# HT62N_v1_1.net
KiCad netlist of a schematic drawn in Altium Designer
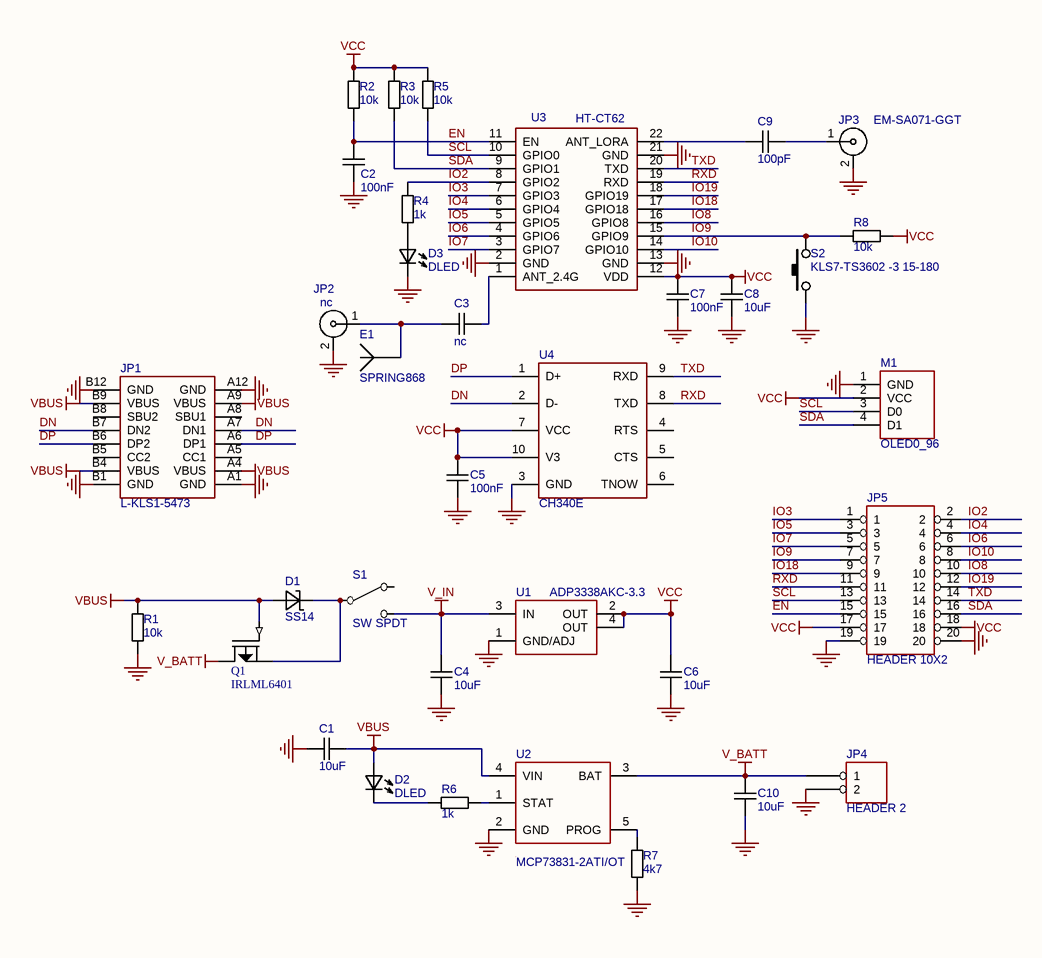
[diagram p0: HT62N_v1.1.SchDoc]

(export (version "E")
  (design (tool "Eeschema 10.0.6"))
  (components
    (comp (ref "C1")
      (value "10uF")
      (footprint "C-0805")
      (fields (field (name "VOLTAGE") "50V"))
      (libsource (lib "Passive") (part "CAPN"))
    )
    (comp (ref "C2")
      (value "100nF")
      (footprint "C-0603")
      (fields (field (name "VOLTAGE") "50V"))
      (libsource (lib "Passive") (part "CAPN"))
    )
    (comp (ref "C3")
      (value "nc")
      (footprint "C-0603")
      (fields (field (name "VOLTAGE") "50V"))
      (libsource (lib "Passive") (part "CAPN"))
    )
    (comp (ref "C4")
      (value "10uF")
      (footprint "C-0805")
      (fields (field (name "VOLTAGE") "50V"))
      (libsource (lib "Passive") (part "CAPN"))
    )
    (comp (ref "C5")
      (value "100nF")
      (footprint "C-0603")
      (fields (field (name "VOLTAGE") "50V"))
      (libsource (lib "Passive") (part "CAPN"))
    )
    (comp (ref "C6")
      (value "10uF")
      (footprint "C-0805")
      (fields (field (name "VOLTAGE") "50V"))
      (libsource (lib "Passive") (part "CAPN"))
    )
    (comp (ref "C7")
      (value "100nF")
      (footprint "C-0603")
      (fields (field (name "VOLTAGE") "50V"))
      (libsource (lib "Passive") (part "CAPN"))
    )
    (comp (ref "C8")
      (value "10uF")
      (footprint "C-0805")
      (fields (field (name "VOLTAGE") "50V"))
      (libsource (lib "Passive") (part "CAPN"))
    )
    (comp (ref "C9")
      (value "100pF")
      (footprint "C-0603")
      (fields (field (name "VOLTAGE") "50V"))
      (libsource (lib "Passive") (part "CAPN"))
    )
    (comp (ref "C10")
      (value "10uF")
      (footprint "C-0805")
      (fields (field (name "VOLTAGE") "50V"))
      (libsource (lib "Passive") (part "CAPN"))
    )
    (comp (ref "D1") (value "SS14") (footprint "D-SMA") (libsource (lib "Diodes") (part "DIODSH")))
    (comp (ref "D2") (value "DLED") (footprint "LED_3mm_RED") (libsource (lib "Diodes") (part "DLED")))
    (comp (ref "D3") (value "DLED") (footprint "LED_3mm_RED") (libsource (lib "Diodes") (part "DLED")))
    (comp (ref "E1") (value "SPRING868") (footprint "ANT_H868_V") (libsource (lib "Passive") (part "ANT")))
    (comp (ref "JP1")
      (value "L-KLS1-5473")
      (footprint "USB_C_SMD_SLOT")
      (libsource (lib "Connectors") (part "L-KLS1-5473"))
    )
    (comp (ref "JP2")
      (value "nc")
      (footprint "SMA_F_EDGE")
      (description "SMA Female R/A PCB Mount")
      (libsource (lib "Connectors") (part "SMA"))
    )
    (comp (ref "JP3")
      (value "EM-SA071-GGT")
      (footprint "SMA_F_EDGE")
      (description "SMA Female R/A PCB Mount")
      (libsource (lib "Connectors") (part "SMA"))
    )
    (comp (ref "JP4")
      (value "HEADER 2")
      (footprint "PLS1-2")
      (libsource (lib "Connectors") (part "HEADER 2"))
    )
    (comp (ref "JP5")
      (value "HEADER 10X2")
      (footprint "PLS2_10")
      (libsource (lib "Connectors") (part "HEADER 10X2"))
    )
    (comp (ref "M1")
      (value "OLED0_96")
      (footprint "OLED096_I2C")
      (libsource (lib "RFmodules") (part "OLED0_96_I2C"))
    )
    (comp (ref "Q1") (value "IRLML6401") (footprint "SOT-23") (libsource (lib "Discrete") (part "MOSF-P")))
    (comp (ref "R1") (value "10k") (footprint "R-0603") (libsource (lib "") (part "RES_2")))
    (comp (ref "R2") (value "10k") (footprint "R-0603") (libsource (lib "Passive") (part "RES")))
    (comp (ref "R3") (value "10k") (footprint "R-0603") (libsource (lib "Passive") (part "RES")))
    (comp (ref "R4") (value "1k") (footprint "R-0603") (libsource (lib "") (part "RES_2")))
    (comp (ref "R5") (value "10k") (footprint "R-0603") (libsource (lib "Passive") (part "RES")))
    (comp (ref "R6") (value "1k") (footprint "R-0603") (libsource (lib "") (part "RES_1")))
    (comp (ref "R7") (value "4k7") (footprint "R-0603") (libsource (lib "") (part "RES_2")))
    (comp (ref "R8") (value "10k") (footprint "R-0603") (libsource (lib "") (part "RES_1")))
    (comp (ref "S1")
      (value "SW SPDT")
      (footprint "SK-12D07VG5")
      (libsource (lib "Switches") (part "SW SPDT"))
    )
    (comp (ref "S2")
      (value "KLS7-TS3602 -3 15-180")
      (footprint "KLS7-TS3602")
      (libsource (lib "Switches") (part "SW-1"))
    )
    (comp (ref "U1")
      (value "ADP3338AKC-3.3")
      (footprint "SOT223")
      (description "LOW CURRENT ADJUSTABLE  VOLTAGE REGULATOR")
      (libsource (lib "ICs") (part "LDL1117"))
    )
    (comp (ref "U2")
      (value "MCP73831-2ATI/OT")
      (footprint "SOT-23-5")
      (fields
        (field (name "LIBRARY PART") "IC`s.SchLib")
        (field (name "FOOTPRINT PART") "IC-package.PcbLib")
        (field (name "MANUFACTURER") "Texas Instruments")
      )
      (libsource (lib "ICs") (part "MCP73831-2ATI/OT"))
    )
    (comp (ref "U3") (value "HT-CT62") (footprint "HT-CT62") (libsource (lib "RFmodules") (part "HT-CT62")))
    (comp (ref "U4") (value "CH340E") (footprint "MSOP-10") (libsource (lib "ICs") (part "CH340E")))
  )
  (nets
    (net (code "1") (name "/DN") (class "Default")
      (node (ref "JP1") (pin "A7") (pinfunction "DN1_A7") (pintype "passive"))
      (node (ref "JP1") (pin "B7") (pinfunction "DN2_B7") (pintype "passive"))
      (node (ref "U4") (pin "2") (pinfunction "D-_2") (pintype "passive"))
    )
    (net (code "2") (name "/DP") (class "Default")
      (node (ref "JP1") (pin "A6") (pinfunction "DP1_A6") (pintype "passive"))
      (node (ref "JP1") (pin "B6") (pinfunction "DP2_B6") (pintype "passive"))
      (node (ref "U4") (pin "1") (pinfunction "D+_1") (pintype "passive"))
    )
    (net (code "3") (name "/EN") (class "Default")
      (node (ref "C2") (pin "2") (pinfunction "2_2") (pintype "passive"))
      (node (ref "JP5") (pin "15") (pinfunction "15_15") (pintype "passive"))
      (node (ref "R2") (pin "2") (pinfunction "2_2") (pintype "passive"))
      (node (ref "U3") (pin "11") (pinfunction "EN_11") (pintype "passive"))
    )
    (net (code "4") (name "/IO2") (class "Default")
      (node (ref "JP5") (pin "2") (pinfunction "2_2") (pintype "passive"))
      (node (ref "R4") (pin "2") (pinfunction "2_2") (pintype "passive"))
      (node (ref "U3") (pin "8") (pinfunction "GPIO2_8") (pintype "passive"))
    )
    (net (code "5") (name "/IO3") (class "Default")
      (node (ref "JP5") (pin "1") (pinfunction "1_1") (pintype "passive"))
      (node (ref "U3") (pin "7") (pinfunction "GPIO3_7") (pintype "passive"))
    )
    (net (code "6") (name "/IO4") (class "Default")
      (node (ref "JP5") (pin "4") (pinfunction "4_4") (pintype "passive"))
      (node (ref "U3") (pin "6") (pinfunction "GPIO4_6") (pintype "passive"))
    )
    (net (code "7") (name "/IO5") (class "Default")
      (node (ref "JP5") (pin "3") (pinfunction "3_3") (pintype "passive"))
      (node (ref "U3") (pin "5") (pinfunction "GPIO5_5") (pintype "passive"))
    )
    (net (code "8") (name "/IO6") (class "Default")
      (node (ref "JP5") (pin "6") (pinfunction "6_6") (pintype "passive"))
      (node (ref "U3") (pin "4") (pinfunction "GPIO6_4") (pintype "passive"))
    )
    (net (code "9") (name "/IO7") (class "Default")
      (node (ref "JP5") (pin "5") (pinfunction "5_5") (pintype "passive"))
      (node (ref "U3") (pin "3") (pinfunction "GPIO7_3") (pintype "passive"))
    )
    (net (code "10") (name "/IO8") (class "Default")
      (node (ref "JP5") (pin "10") (pinfunction "10_10") (pintype "passive"))
      (node (ref "U3") (pin "16") (pinfunction "GPIO8_16") (pintype "passive"))
    )
    (net (code "11") (name "/IO9") (class "Default")
      (node (ref "JP5") (pin "7") (pinfunction "7_7") (pintype "passive"))
      (node (ref "R8") (pin "2") (pinfunction "2_2") (pintype "passive"))
      (node (ref "S2") (pin "2") (pinfunction "2_2") (pintype "passive"))
      (node (ref "U3") (pin "15") (pinfunction "GPIO9_15") (pintype "passive"))
    )
    (net (code "12") (name "/IO10") (class "Default")
      (node (ref "JP5") (pin "8") (pinfunction "8_8") (pintype "passive"))
      (node (ref "U3") (pin "14") (pinfunction "GPIO10_14") (pintype "passive"))
    )
    (net (code "13") (name "/IO18") (class "Default")
      (node (ref "JP5") (pin "9") (pinfunction "9_9") (pintype "passive"))
      (node (ref "U3") (pin "17") (pinfunction "GPIO18_17") (pintype "passive"))
    )
    (net (code "14") (name "/IO19") (class "Default")
      (node (ref "JP5") (pin "12") (pinfunction "12_12") (pintype "passive"))
      (node (ref "U3") (pin "18") (pinfunction "GPIO19_18") (pintype "passive"))
    )
    (net (code "15") (name "/RXD") (class "Default")
      (node (ref "JP5") (pin "11") (pinfunction "11_11") (pintype "passive"))
      (node (ref "U3") (pin "19") (pinfunction "RXD_19") (pintype "passive"))
      (node (ref "U4") (pin "8") (pinfunction "TXD_8") (pintype "passive"))
    )
    (net (code "16") (name "/SCL") (class "Default")
      (node (ref "JP5") (pin "13") (pinfunction "13_13") (pintype "passive"))
      (node (ref "M1") (pin "3") (pinfunction "D0_3") (pintype "passive"))
      (node (ref "R5") (pin "2") (pinfunction "2_2") (pintype "passive"))
      (node (ref "U3") (pin "10") (pinfunction "GPIO0_10") (pintype "passive"))
    )
    (net (code "17") (name "/SDA") (class "Default")
      (node (ref "JP5") (pin "16") (pinfunction "16_16") (pintype "passive"))
      (node (ref "M1") (pin "4") (pinfunction "D1_4") (pintype "passive"))
      (node (ref "R3") (pin "2") (pinfunction "2_2") (pintype "passive"))
      (node (ref "U3") (pin "9") (pinfunction "GPIO1_9") (pintype "passive"))
    )
    (net (code "18") (name "/TXD") (class "Default")
      (node (ref "JP5") (pin "14") (pinfunction "14_14") (pintype "passive"))
      (node (ref "U3") (pin "20") (pinfunction "TXD_20") (pintype "passive"))
      (node (ref "U4") (pin "9") (pinfunction "RXD_9") (pintype "passive"))
    )
    (net (code "19") (name "GND") (class "Default")
      (node (ref "C1") (pin "1") (pinfunction "1_1") (pintype "passive"))
      (node (ref "C10") (pin "1") (pinfunction "1_1") (pintype "passive"))
      (node (ref "C2") (pin "1") (pinfunction "1_1") (pintype "passive"))
      (node (ref "C4") (pin "2") (pinfunction "2_2") (pintype "passive"))
      (node (ref "C5") (pin "1") (pinfunction "1_1") (pintype "passive"))
      (node (ref "C6") (pin "2") (pinfunction "2_2") (pintype "passive"))
      (node (ref "C7") (pin "1") (pinfunction "1_1") (pintype "passive"))
      (node (ref "C8") (pin "2") (pinfunction "2_2") (pintype "passive"))
      (node (ref "D3") (pin "2") (pinfunction "2_2") (pintype "passive"))
      (node (ref "JP1") (pin "A1") (pinfunction "GND_A1") (pintype "passive"))
      (node (ref "JP1") (pin "A12") (pinfunction "GND_A12") (pintype "passive"))
      (node (ref "JP1") (pin "B1") (pinfunction "GND_B1") (pintype "passive"))
      (node (ref "JP1") (pin "B12") (pinfunction "GND_B12") (pintype "passive"))
      (node (ref "JP2") (pin "2") (pinfunction "2_2") (pintype "passive"))
      (node (ref "JP3") (pin "2") (pinfunction "2_2") (pintype "passive"))
      (node (ref "JP4") (pin "2") (pinfunction "2_2") (pintype "passive"))
      (node (ref "JP5") (pin "19") (pinfunction "19_19") (pintype "passive"))
      (node (ref "JP5") (pin "20") (pinfunction "20_20") (pintype "passive"))
      (node (ref "M1") (pin "1") (pinfunction "GND_1") (pintype "passive"))
      (node (ref "R1") (pin "1") (pinfunction "1_1") (pintype "passive"))
      (node (ref "R7") (pin "1") (pinfunction "1_1") (pintype "passive"))
      (node (ref "S2") (pin "1") (pinfunction "1_1") (pintype "passive"))
      (node (ref "U1") (pin "1") (pinfunction "GND/ADJ_1") (pintype "power_in"))
      (node (ref "U2") (pin "2") (pinfunction "GND_2") (pintype "passive"))
      (node (ref "U3") (pin "13") (pinfunction "GND_13") (pintype "passive"))
      (node (ref "U3") (pin "2") (pinfunction "GND_2") (pintype "passive"))
      (node (ref "U3") (pin "21") (pinfunction "GND_21") (pintype "passive"))
      (node (ref "U4") (pin "3") (pinfunction "GND_3") (pintype "passive"))
    )
    (net (code "20") (name "Net-(C3-Pad1)") (class "Default")
      (node (ref "C3") (pin "1") (pinfunction "1_1") (pintype "passive"))
      (node (ref "E1") (pin "1") (pinfunction "1_1") (pintype "passive"))
      (node (ref "JP2") (pin "1") (pinfunction "1_1") (pintype "passive"))
    )
    (net (code "21") (name "Net-(C9-Pad2)") (class "Default")
      (node (ref "C9") (pin "2") (pinfunction "2_2") (pintype "passive"))
      (node (ref "JP3") (pin "1") (pinfunction "1_1") (pintype "passive"))
    )
    (net (code "22") (name "Net-(D2-Pad2)") (class "Default")
      (node (ref "D2") (pin "2") (pinfunction "2_2") (pintype "passive"))
      (node (ref "R6") (pin "2") (pinfunction "2_2") (pintype "passive"))
    )
    (net (code "23") (name "Net-(D3-Pad1)") (class "Default")
      (node (ref "D3") (pin "1") (pinfunction "1_1") (pintype "passive"))
      (node (ref "R4") (pin "1") (pinfunction "1_1") (pintype "passive"))
    )
    (net (code "24") (name "Net-(Q1-SOURCE)") (class "Default")
      (node (ref "D1") (pin "2") (pinfunction "2_2") (pintype "passive"))
      (node (ref "Q1") (pin "2") (pinfunction "SOURCE_2") (pintype "passive"))
      (node (ref "S1") (pin "2") (pinfunction "COMMON_2") (pintype "passive"))
    )
    (net (code "25") (name "Net-(U2-PROG)") (class "Default")
      (node (ref "R7") (pin "2") (pinfunction "2_2") (pintype "passive"))
      (node (ref "U2") (pin "5") (pinfunction "PROG_5") (pintype "passive"))
    )
    (net (code "26") (name "Net-(U2-STAT)") (class "Default")
      (node (ref "R6") (pin "1") (pinfunction "1_1") (pintype "passive"))
      (node (ref "U2") (pin "1") (pinfunction "STAT_1") (pintype "passive"))
    )
    (net (code "27") (name "Net-(U3-ANT_2.4G)") (class "Default")
      (node (ref "C3") (pin "2") (pinfunction "2_2") (pintype "passive"))
      (node (ref "U3") (pin "1") (pinfunction "ANT_2.4G_1") (pintype "passive"))
    )
    (net (code "28") (name "Net-(U3-ANT_LORA)") (class "Default")
      (node (ref "C9") (pin "1") (pinfunction "1_1") (pintype "passive"))
      (node (ref "U3") (pin "22") (pinfunction "ANT_LORA_22") (pintype "passive"))
    )
    (net (code "29") (name "VBUS") (class "Default")
      (node (ref "C1") (pin "2") (pinfunction "2_2") (pintype "passive"))
      (node (ref "D1") (pin "1") (pinfunction "1_1") (pintype "passive"))
      (node (ref "D2") (pin "1") (pinfunction "1_1") (pintype "passive"))
      (node (ref "JP1") (pin "A4") (pinfunction "VBUS_A4") (pintype "passive"))
      (node (ref "JP1") (pin "A9") (pinfunction "VBUS_A9") (pintype "passive"))
      (node (ref "JP1") (pin "B4") (pinfunction "VBUS_B4") (pintype "passive"))
      (node (ref "JP1") (pin "B9") (pinfunction "VBUS_B9") (pintype "passive"))
      (node (ref "Q1") (pin "1") (pinfunction "GATE_1") (pintype "input"))
      (node (ref "R1") (pin "2") (pinfunction "2_2") (pintype "passive"))
      (node (ref "U2") (pin "4") (pinfunction "VIN_4") (pintype "passive"))
    )
    (net (code "30") (name "VCC") (class "Default")
      (node (ref "C5") (pin "2") (pinfunction "2_2") (pintype "passive"))
      (node (ref "C6") (pin "1") (pinfunction "1_1") (pintype "passive"))
      (node (ref "C7") (pin "2") (pinfunction "2_2") (pintype "passive"))
      (node (ref "C8") (pin "1") (pinfunction "1_1") (pintype "passive"))
      (node (ref "JP5") (pin "17") (pinfunction "17_17") (pintype "passive"))
      (node (ref "JP5") (pin "18") (pinfunction "18_18") (pintype "passive"))
      (node (ref "M1") (pin "2") (pinfunction "VCC_2") (pintype "passive"))
      (node (ref "R2") (pin "1") (pinfunction "1_1") (pintype "passive"))
      (node (ref "R3") (pin "1") (pinfunction "1_1") (pintype "passive"))
      (node (ref "R5") (pin "1") (pinfunction "1_1") (pintype "passive"))
      (node (ref "R8") (pin "1") (pinfunction "1_1") (pintype "passive"))
      (node (ref "U1") (pin "2") (pinfunction "OUT_2") (pintype "power_in"))
      (node (ref "U1") (pin "4") (pinfunction "OUT_4") (pintype "power_in"))
      (node (ref "U3") (pin "12") (pinfunction "VDD_12") (pintype "passive"))
      (node (ref "U4") (pin "10") (pinfunction "V3_10") (pintype "passive"))
      (node (ref "U4") (pin "7") (pinfunction "VCC_7") (pintype "passive"))
    )
    (net (code "31") (name "VSS") (class "Default")
      (node (ref "JP1") (pin "17") (pinfunction "VSS_17") (pintype "power_in"))
    )
    (net (code "32") (name "V_BATT") (class "Default")
      (node (ref "C10") (pin "2") (pinfunction "2_2") (pintype "passive"))
      (node (ref "JP4") (pin "1") (pinfunction "1_1") (pintype "passive"))
      (node (ref "Q1") (pin "3") (pinfunction "DRAIN_3") (pintype "passive"))
      (node (ref "U2") (pin "3") (pinfunction "BAT_3") (pintype "passive"))
    )
    (net (code "33") (name "V_IN") (class "Default")
      (node (ref "C4") (pin "1") (pinfunction "1_1") (pintype "passive"))
      (node (ref "S1") (pin "3") (pinfunction "NO_3") (pintype "passive"))
      (node (ref "U1") (pin "3") (pinfunction "IN_3") (pintype "power_in"))
    )
    (net (code "34") (name "unconnected-(JP1-CC1-PadA5)") (class "Default")
      (node (ref "JP1") (pin "A5") (pinfunction "CC1_A5") (pintype "passive"))
    )
    (net (code "35") (name "unconnected-(JP1-CC2-PadB5)") (class "Default")
      (node (ref "JP1") (pin "B5") (pinfunction "CC2_B5") (pintype "passive"))
    )
    (net (code "36") (name "unconnected-(JP1-SBU1-PadA8)") (class "Default")
      (node (ref "JP1") (pin "A8") (pinfunction "SBU1_A8") (pintype "passive"))
    )
    (net (code "37") (name "unconnected-(JP1-SBU2-PadB8)") (class "Default")
      (node (ref "JP1") (pin "B8") (pinfunction "SBU2_B8") (pintype "passive"))
    )
    (net (code "38") (name "unconnected-(S1-NC-Pad1)") (class "Default")
      (node (ref "S1") (pin "1") (pinfunction "NC_1") (pintype "passive"))
    )
    (net (code "39") (name "unconnected-(U4-CTS-Pad5)") (class "Default")
      (node (ref "U4") (pin "5") (pinfunction "CTS_5") (pintype "passive"))
    )
    (net (code "40") (name "unconnected-(U4-RTS-Pad4)") (class "Default")
      (node (ref "U4") (pin "4") (pinfunction "RTS_4") (pintype "passive"))
    )
    (net (code "41") (name "unconnected-(U4-TNOW-Pad6)") (class "Default")
      (node (ref "U4") (pin "6") (pinfunction "TNOW_6") (pintype "passive"))
    )
  )
)
